# SkyKontrol-slotExpansion.net
KiCad netlist of a schematic drawn in EAGLE
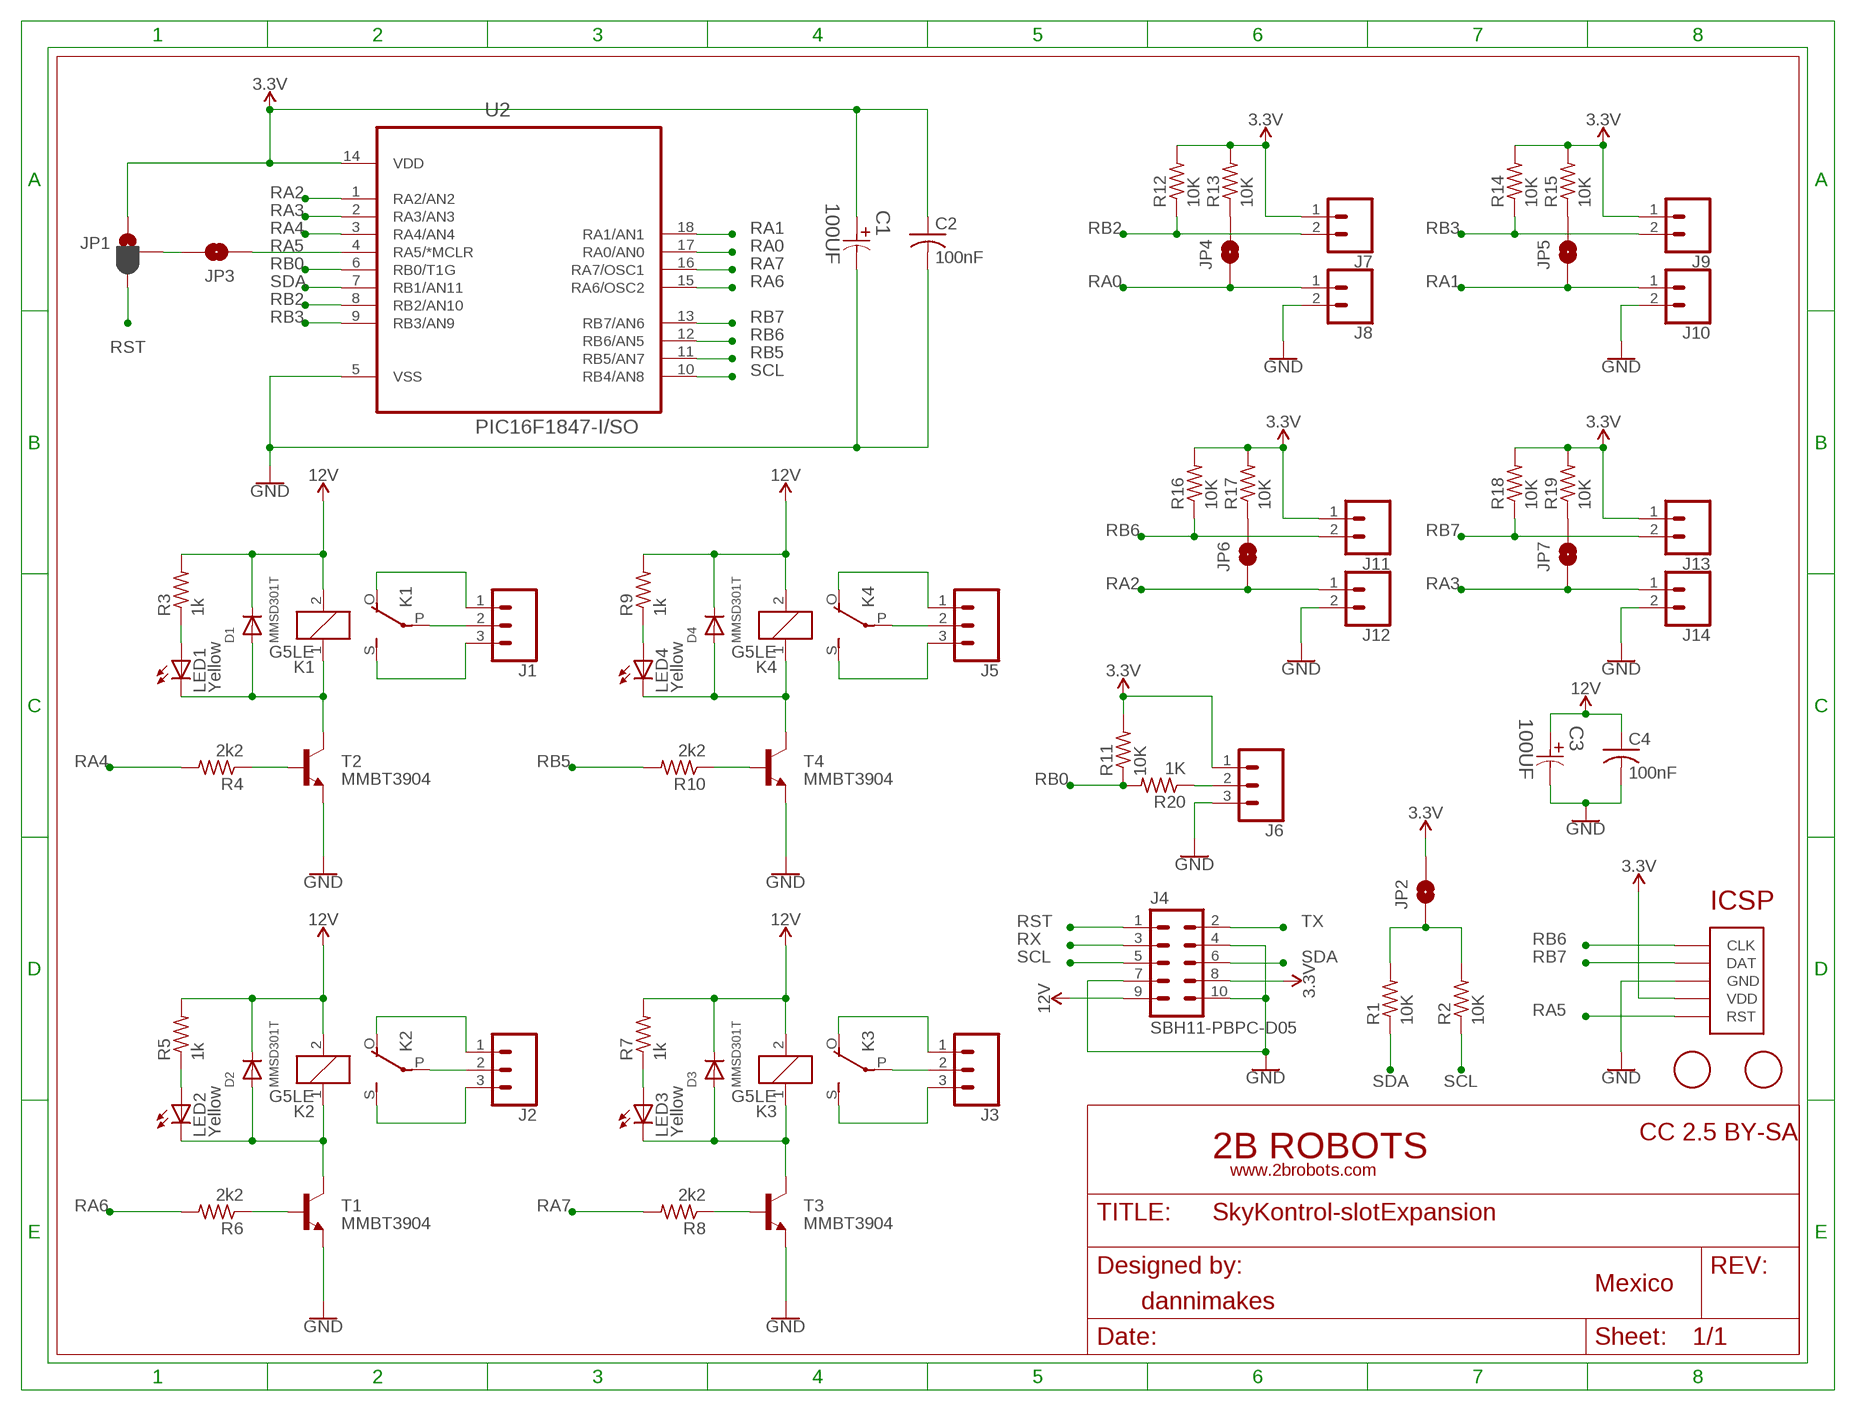
[diagram p0: schematic, sheet 1]

(export (version "E")
  (design (tool "Eeschema 10.0.6"))
  (components
    (comp (ref "C1")
      (value "100UF")
      (footprint "eagle-import:CAPAE660X800N")
      (fields (field (name "MPN") "EEE-HA1E101XP") (field (name "TOLERANCE") "±20 %"))
      (libsource (lib "eagle-import") (part "EEE--CASE-D8HA1E101XP"))
    )
    (comp (ref "C2")
      (value "100nF")
      (footprint "eagle-import:C0603K")
      (libsource (lib "eagle-import") (part "C-USC0603K"))
    )
    (comp (ref "C3")
      (value "100UF")
      (footprint "eagle-import:CAPAE660X800N")
      (fields (field (name "MPN") "EEE-HA1E101XP") (field (name "TOLERANCE") "±20 %"))
      (libsource (lib "eagle-import") (part "EEE--CASE-D8HA1E101XP"))
    )
    (comp (ref "C4")
      (value "100nF")
      (footprint "eagle-import:C0603K")
      (libsource (lib "eagle-import") (part "C-USC0603K"))
    )
    (comp (ref "D1")
      (value "MMSD301T")
      (footprint "eagle-import:SOD-123")
      (libsource (lib "eagle-import") (part "DIODESOD-123"))
    )
    (comp (ref "D2")
      (value "MMSD301T")
      (footprint "eagle-import:SOD-123")
      (libsource (lib "eagle-import") (part "DIODESOD-123"))
    )
    (comp (ref "D3")
      (value "MMSD301T")
      (footprint "eagle-import:SOD-123")
      (libsource (lib "eagle-import") (part "DIODESOD-123"))
    )
    (comp (ref "D4")
      (value "MMSD301T")
      (footprint "eagle-import:SOD-123")
      (libsource (lib "eagle-import") (part "DIODESOD-123"))
    )
    (comp (ref "J1")
      (value "CONN_03-SCREW-5MM")
      (footprint "eagle-import:SCREWTERMINAL-5MM-3")
      (libsource (lib "eagle-import") (part "CONN_03-SCREW-5MM"))
    )
    (comp (ref "J2")
      (value "CONN_03-SCREW-5MM")
      (footprint "eagle-import:SCREWTERMINAL-5MM-3")
      (libsource (lib "eagle-import") (part "CONN_03-SCREW-5MM"))
    )
    (comp (ref "J3")
      (value "CONN_03-SCREW-5MM")
      (footprint "eagle-import:SCREWTERMINAL-5MM-3")
      (libsource (lib "eagle-import") (part "CONN_03-SCREW-5MM"))
    )
    (comp (ref "J4")
      (value "SBH11-PBPC-D05")
      (footprint "eagle-import:SBH11-PBPC-D05")
      (libsource (lib "eagle-import") (part "SBH11-PBPC-D05"))
    )
    (comp (ref "J5")
      (value "CONN_03-SCREW-5MM")
      (footprint "eagle-import:SCREWTERMINAL-5MM-3")
      (libsource (lib "eagle-import") (part "CONN_03-SCREW-5MM"))
    )
    (comp (ref "J6")
      (value "CONN_03-SCREW-5MM")
      (footprint "eagle-import:SCREWTERMINAL-5MM-3")
      (libsource (lib "eagle-import") (part "CONN_03-SCREW-5MM"))
    )
    (comp (ref "J7")
      (value "CONN_025MM")
      (footprint "eagle-import:SCREWTERMINAL-5MM-2")
      (libsource (lib "eagle-import") (part "CONN_025MM"))
    )
    (comp (ref "J8")
      (value "CONN_025MM")
      (footprint "eagle-import:SCREWTERMINAL-5MM-2")
      (libsource (lib "eagle-import") (part "CONN_025MM"))
    )
    (comp (ref "J9")
      (value "CONN_025MM")
      (footprint "eagle-import:SCREWTERMINAL-5MM-2")
      (libsource (lib "eagle-import") (part "CONN_025MM"))
    )
    (comp (ref "J10")
      (value "CONN_025MM")
      (footprint "eagle-import:SCREWTERMINAL-5MM-2")
      (libsource (lib "eagle-import") (part "CONN_025MM"))
    )
    (comp (ref "J11")
      (value "CONN_025MM")
      (footprint "eagle-import:SCREWTERMINAL-5MM-2")
      (libsource (lib "eagle-import") (part "CONN_025MM"))
    )
    (comp (ref "J12")
      (value "CONN_025MM")
      (footprint "eagle-import:SCREWTERMINAL-5MM-2")
      (libsource (lib "eagle-import") (part "CONN_025MM"))
    )
    (comp (ref "J13")
      (value "CONN_025MM")
      (footprint "eagle-import:SCREWTERMINAL-5MM-2")
      (libsource (lib "eagle-import") (part "CONN_025MM"))
    )
    (comp (ref "J14")
      (value "CONN_025MM")
      (footprint "eagle-import:SCREWTERMINAL-5MM-2")
      (libsource (lib "eagle-import") (part "CONN_025MM"))
    )
    (comp (ref "JP1")
      (value "JUMPER-SMT_3_1-NC_PASTE_SILK")
      (footprint "eagle-import:SMT-JUMPER_3_1-NC_PASTE_SILK")
      (libsource (lib "eagle-import") (part "JUMPER-SMT_3_1-NC_PASTE_SILK"))
    )
    (comp (ref "JP2")
      (value "JUMPER-SMT_2_NO_SILK")
      (footprint "eagle-import:SMT-JUMPER_2_NO_SILK")
      (libsource (lib "eagle-import") (part "JUMPER-SMT_2_NO_SILK"))
    )
    (comp (ref "JP3")
      (value "JUMPER-SMT_2_NO_SILK")
      (footprint "eagle-import:SMT-JUMPER_2_NO_SILK")
      (libsource (lib "eagle-import") (part "JUMPER-SMT_2_NO_SILK"))
    )
    (comp (ref "JP4")
      (value "JUMPER-SMT_2_NO_SILK")
      (footprint "eagle-import:SMT-JUMPER_2_NO_SILK")
      (libsource (lib "eagle-import") (part "JUMPER-SMT_2_NO_SILK"))
    )
    (comp (ref "JP5")
      (value "JUMPER-SMT_2_NO_SILK")
      (footprint "eagle-import:SMT-JUMPER_2_NO_SILK")
      (libsource (lib "eagle-import") (part "JUMPER-SMT_2_NO_SILK"))
    )
    (comp (ref "JP6")
      (value "JUMPER-SMT_2_NO_SILK")
      (footprint "eagle-import:SMT-JUMPER_2_NO_SILK")
      (libsource (lib "eagle-import") (part "JUMPER-SMT_2_NO_SILK"))
    )
    (comp (ref "JP7")
      (value "JUMPER-SMT_2_NO_SILK")
      (footprint "eagle-import:SMT-JUMPER_2_NO_SILK")
      (libsource (lib "eagle-import") (part "JUMPER-SMT_2_NO_SILK"))
    )
    (comp (ref "K1")
      (value "G5LE")
      (footprint "eagle-import:G5LE")
      (libsource (lib "eagle-import") (part "G5LE"))
    )
    (comp (ref "K2")
      (value "G5LE")
      (footprint "eagle-import:G5LE")
      (libsource (lib "eagle-import") (part "G5LE"))
    )
    (comp (ref "K3")
      (value "G5LE")
      (footprint "eagle-import:G5LE")
      (libsource (lib "eagle-import") (part "G5LE"))
    )
    (comp (ref "K4")
      (value "G5LE")
      (footprint "eagle-import:G5LE")
      (libsource (lib "eagle-import") (part "G5LE"))
    )
    (comp (ref "LED1")
      (value "Yellow")
      (footprint "eagle-import:CHIPLED_1206")
      (libsource (lib "eagle-import") (part "LEDCHIPLED_1206"))
    )
    (comp (ref "LED2")
      (value "Yellow")
      (footprint "eagle-import:CHIPLED_1206")
      (libsource (lib "eagle-import") (part "LEDCHIPLED_1206"))
    )
    (comp (ref "LED3")
      (value "Yellow")
      (footprint "eagle-import:CHIPLED_1206")
      (libsource (lib "eagle-import") (part "LEDCHIPLED_1206"))
    )
    (comp (ref "LED4")
      (value "Yellow")
      (footprint "eagle-import:CHIPLED_1206")
      (libsource (lib "eagle-import") (part "LEDCHIPLED_1206"))
    )
    (comp (ref "R1")
      (value "10K")
      (footprint "eagle-import:R0805")
      (libsource (lib "eagle-import") (part "R-US_R0805"))
    )
    (comp (ref "R2")
      (value "10K")
      (footprint "eagle-import:R0805")
      (libsource (lib "eagle-import") (part "R-US_R0805"))
    )
    (comp (ref "R3")
      (value "1k")
      (footprint "eagle-import:R0805")
      (libsource (lib "eagle-import") (part "R-US_R0805"))
    )
    (comp (ref "R4")
      (value "2k2")
      (footprint "eagle-import:R0805")
      (libsource (lib "eagle-import") (part "R-US_R0805"))
    )
    (comp (ref "R5")
      (value "1k")
      (footprint "eagle-import:R0805")
      (libsource (lib "eagle-import") (part "R-US_R0805"))
    )
    (comp (ref "R6")
      (value "2k2")
      (footprint "eagle-import:R0805")
      (libsource (lib "eagle-import") (part "R-US_R0805"))
    )
    (comp (ref "R7")
      (value "1k")
      (footprint "eagle-import:R0805")
      (libsource (lib "eagle-import") (part "R-US_R0805"))
    )
    (comp (ref "R8")
      (value "2k2")
      (footprint "eagle-import:R0805")
      (libsource (lib "eagle-import") (part "R-US_R0805"))
    )
    (comp (ref "R9")
      (value "1k")
      (footprint "eagle-import:R0805")
      (libsource (lib "eagle-import") (part "R-US_R0805"))
    )
    (comp (ref "R10")
      (value "2k2")
      (footprint "eagle-import:R0805")
      (libsource (lib "eagle-import") (part "R-US_R0805"))
    )
    (comp (ref "R11")
      (value "10K")
      (footprint "eagle-import:R0805")
      (libsource (lib "eagle-import") (part "R-US_R0805"))
    )
    (comp (ref "R12")
      (value "10K")
      (footprint "eagle-import:R0805")
      (libsource (lib "eagle-import") (part "R-US_R0805"))
    )
    (comp (ref "R13")
      (value "10K")
      (footprint "eagle-import:R0805")
      (libsource (lib "eagle-import") (part "R-US_R0805"))
    )
    (comp (ref "R14")
      (value "10K")
      (footprint "eagle-import:R0805")
      (libsource (lib "eagle-import") (part "R-US_R0805"))
    )
    (comp (ref "R15")
      (value "10K")
      (footprint "eagle-import:R0805")
      (libsource (lib "eagle-import") (part "R-US_R0805"))
    )
    (comp (ref "R16")
      (value "10K")
      (footprint "eagle-import:R0805")
      (libsource (lib "eagle-import") (part "R-US_R0805"))
    )
    (comp (ref "R17")
      (value "10K")
      (footprint "eagle-import:R0805")
      (libsource (lib "eagle-import") (part "R-US_R0805"))
    )
    (comp (ref "R18")
      (value "10K")
      (footprint "eagle-import:R0805")
      (libsource (lib "eagle-import") (part "R-US_R0805"))
    )
    (comp (ref "R19")
      (value "10K")
      (footprint "eagle-import:R0805")
      (libsource (lib "eagle-import") (part "R-US_R0805"))
    )
    (comp (ref "R20")
      (value "1K")
      (footprint "eagle-import:R0805")
      (libsource (lib "eagle-import") (part "R-US_R0805"))
    )
    (comp (ref "T1")
      (value "MMBT3904")
      (footprint "eagle-import:SOT23-BEC")
      (libsource (lib "eagle-import") (part "-NPN-SOT23-BECMMBT3904LT1"))
    )
    (comp (ref "T2")
      (value "MMBT3904")
      (footprint "eagle-import:SOT23-BEC")
      (libsource (lib "eagle-import") (part "-NPN-SOT23-BECMMBT3904LT1"))
    )
    (comp (ref "T3")
      (value "MMBT3904")
      (footprint "eagle-import:SOT23-BEC")
      (libsource (lib "eagle-import") (part "-NPN-SOT23-BECMMBT3904LT1"))
    )
    (comp (ref "T4")
      (value "MMBT3904")
      (footprint "eagle-import:SOT23-BEC")
      (libsource (lib "eagle-import") (part "-NPN-SOT23-BECMMBT3904LT1"))
    )
    (comp (ref "U$1")
      (value "FIDUCIAL")
      (footprint "eagle-import:FIDUCIAL_1MM")
      (libsource (lib "eagle-import") (part "FIDUCIAL"))
    )
    (comp (ref "U$2")
      (value "ICSP_POGO")
      (footprint "eagle-import:ICSP_POGO")
      (libsource (lib "eagle-import") (part "ICSP_POGO"))
    )
    (comp (ref "U$3")
      (value "FIDUCIAL")
      (footprint "eagle-import:FIDUCIAL_1MM")
      (libsource (lib "eagle-import") (part "FIDUCIAL"))
    )
    (comp (ref "U2")
      (value "PIC16F1847-I/SO")
      (footprint "eagle-import:SOIC127P1030X265-18N")
      (libsource (lib "eagle-import") (part "PIC16F1847-I/SO"))
    )
  )
  (nets
    (net (code "1") (name "/RA0") (class "Default")
      (node (ref "J8") (pin "1") (pinfunction "1_1") (pintype "passive"))
      (node (ref "JP4") (pin "1") (pinfunction "1_1") (pintype "passive"))
      (node (ref "U2") (pin "17") (pinfunction "RA0/AN0_17") (pintype "bidirectional"))
    )
    (net (code "2") (name "/RA1") (class "Default")
      (node (ref "J10") (pin "1") (pinfunction "1_1") (pintype "passive"))
      (node (ref "JP5") (pin "1") (pinfunction "1_1") (pintype "passive"))
      (node (ref "U2") (pin "18") (pinfunction "RA1/AN1_18") (pintype "bidirectional"))
    )
    (net (code "3") (name "/RA2") (class "Default")
      (node (ref "J12") (pin "1") (pinfunction "1_1") (pintype "passive"))
      (node (ref "JP6") (pin "1") (pinfunction "1_1") (pintype "passive"))
      (node (ref "U2") (pin "1") (pinfunction "RA2/AN2_1") (pintype "bidirectional"))
    )
    (net (code "4") (name "/RA3") (class "Default")
      (node (ref "J14") (pin "1") (pinfunction "1_1") (pintype "passive"))
      (node (ref "JP7") (pin "1") (pinfunction "1_1") (pintype "passive"))
      (node (ref "U2") (pin "2") (pinfunction "RA3/AN3_2") (pintype "bidirectional"))
    )
    (net (code "5") (name "/RA4") (class "Default")
      (node (ref "R4") (pin "2") (pinfunction "2_2") (pintype "passive"))
      (node (ref "U2") (pin "3") (pinfunction "RA4/AN4_3") (pintype "bidirectional"))
    )
    (net (code "6") (name "/RA5") (class "Default")
      (node (ref "JP3") (pin "1") (pinfunction "1_1") (pintype "passive"))
      (node (ref "U$2") (pin "P$1") (pinfunction "RST_P$1") (pintype "bidirectional"))
      (node (ref "U2") (pin "4") (pinfunction "RA5/*MCLR_4") (pintype "bidirectional"))
    )
    (net (code "7") (name "/RA6") (class "Default")
      (node (ref "R6") (pin "2") (pinfunction "2_2") (pintype "passive"))
      (node (ref "U2") (pin "15") (pinfunction "RA6/OSC2_15") (pintype "bidirectional"))
    )
    (net (code "8") (name "/RA7") (class "Default")
      (node (ref "R8") (pin "2") (pinfunction "2_2") (pintype "passive"))
      (node (ref "U2") (pin "16") (pinfunction "RA7/OSC1_16") (pintype "bidirectional"))
    )
    (net (code "9") (name "/RB0") (class "Default")
      (node (ref "R11") (pin "1") (pinfunction "1_1") (pintype "passive"))
      (node (ref "R20") (pin "2") (pinfunction "2_2") (pintype "passive"))
      (node (ref "U2") (pin "6") (pinfunction "RB0/T1G_6") (pintype "bidirectional"))
    )
    (net (code "10") (name "/RB2") (class "Default")
      (node (ref "J7") (pin "2") (pinfunction "2_2") (pintype "passive"))
      (node (ref "R12") (pin "1") (pinfunction "1_1") (pintype "passive"))
      (node (ref "U2") (pin "8") (pinfunction "RB2/AN10_8") (pintype "bidirectional"))
    )
    (net (code "11") (name "/RB3") (class "Default")
      (node (ref "J9") (pin "2") (pinfunction "2_2") (pintype "passive"))
      (node (ref "R14") (pin "1") (pinfunction "1_1") (pintype "passive"))
      (node (ref "U2") (pin "9") (pinfunction "RB3/AN9_9") (pintype "bidirectional"))
    )
    (net (code "12") (name "/RB5") (class "Default")
      (node (ref "R10") (pin "2") (pinfunction "2_2") (pintype "passive"))
      (node (ref "U2") (pin "11") (pinfunction "RB5/AN7_11") (pintype "bidirectional"))
    )
    (net (code "13") (name "/RB6") (class "Default")
      (node (ref "J11") (pin "2") (pinfunction "2_2") (pintype "passive"))
      (node (ref "R16") (pin "1") (pinfunction "1_1") (pintype "passive"))
      (node (ref "U$2") (pin "P$5") (pinfunction "CLK_P$5") (pintype "bidirectional"))
      (node (ref "U2") (pin "12") (pinfunction "RB6/AN5_12") (pintype "bidirectional"))
    )
    (net (code "14") (name "/RB7") (class "Default")
      (node (ref "J13") (pin "2") (pinfunction "2_2") (pintype "passive"))
      (node (ref "R18") (pin "1") (pinfunction "1_1") (pintype "passive"))
      (node (ref "U$2") (pin "P$4") (pinfunction "DAT_P$4") (pintype "bidirectional"))
      (node (ref "U2") (pin "13") (pinfunction "RB7/AN6_13") (pintype "bidirectional"))
    )
    (net (code "15") (name "/RST") (class "Default")
      (node (ref "J4") (pin "1") (pinfunction "1_1") (pintype "passive"))
      (node (ref "JP1") (pin "3") (pinfunction "3_3") (pintype "passive"))
    )
    (net (code "16") (name "/RX") (class "Default")
      (node (ref "J4") (pin "3") (pinfunction "3_3") (pintype "passive"))
    )
    (net (code "17") (name "/SCL") (class "Default")
      (node (ref "J4") (pin "5") (pinfunction "5_5") (pintype "passive"))
      (node (ref "R2") (pin "1") (pinfunction "1_1") (pintype "passive"))
      (node (ref "U2") (pin "10") (pinfunction "RB4/AN8_10") (pintype "bidirectional"))
    )
    (net (code "18") (name "/SDA") (class "Default")
      (node (ref "J4") (pin "6") (pinfunction "6_6") (pintype "passive"))
      (node (ref "R1") (pin "1") (pinfunction "1_1") (pintype "passive"))
      (node (ref "U2") (pin "7") (pinfunction "RB1/AN11_7") (pintype "bidirectional"))
    )
    (net (code "19") (name "/TX") (class "Default")
      (node (ref "J4") (pin "2") (pinfunction "2_2") (pintype "passive"))
    )
    (net (code "20") (name "3.3V") (class "Default")
      (node (ref "C1") (pin "1") (pinfunction "1_1") (pintype "passive"))
      (node (ref "C2") (pin "1") (pinfunction "1_1") (pintype "passive"))
      (node (ref "J11") (pin "1") (pinfunction "1_1") (pintype "passive"))
      (node (ref "J13") (pin "1") (pinfunction "1_1") (pintype "passive"))
      (node (ref "J4") (pin "8") (pinfunction "8_8") (pintype "passive"))
      (node (ref "J6") (pin "1") (pinfunction "1_1") (pintype "passive"))
      (node (ref "J7") (pin "1") (pinfunction "1_1") (pintype "passive"))
      (node (ref "J9") (pin "1") (pinfunction "1_1") (pintype "passive"))
      (node (ref "JP1") (pin "1") (pinfunction "1_1") (pintype "passive"))
      (node (ref "JP2") (pin "2") (pinfunction "2_2") (pintype "passive"))
      (node (ref "R11") (pin "2") (pinfunction "2_2") (pintype "passive"))
      (node (ref "R12") (pin "2") (pinfunction "2_2") (pintype "passive"))
      (node (ref "R13") (pin "2") (pinfunction "2_2") (pintype "passive"))
      (node (ref "R14") (pin "2") (pinfunction "2_2") (pintype "passive"))
      (node (ref "R15") (pin "2") (pinfunction "2_2") (pintype "passive"))
      (node (ref "R16") (pin "2") (pinfunction "2_2") (pintype "passive"))
      (node (ref "R17") (pin "2") (pinfunction "2_2") (pintype "passive"))
      (node (ref "R18") (pin "2") (pinfunction "2_2") (pintype "passive"))
      (node (ref "R19") (pin "2") (pinfunction "2_2") (pintype "passive"))
      (node (ref "U$2") (pin "P$2") (pinfunction "VDD_P$2") (pintype "bidirectional"))
      (node (ref "U2") (pin "14") (pinfunction "VDD_14") (pintype "power_in"))
    )
    (net (code "21") (name "12V") (class "Default")
      (node (ref "C3") (pin "1") (pinfunction "1_1") (pintype "passive"))
      (node (ref "C4") (pin "1") (pinfunction "1_1") (pintype "passive"))
      (node (ref "D1") (pin "C") (pinfunction "C_C") (pintype "passive"))
      (node (ref "D2") (pin "C") (pinfunction "C_C") (pintype "passive"))
      (node (ref "D3") (pin "C") (pinfunction "C_C") (pintype "passive"))
      (node (ref "D4") (pin "C") (pinfunction "C_C") (pintype "passive"))
      (node (ref "J4") (pin "9") (pinfunction "9_9") (pintype "passive"))
      (node (ref "K1") (pin "2") (pinfunction "2_2") (pintype "passive"))
      (node (ref "K2") (pin "2") (pinfunction "2_2") (pintype "passive"))
      (node (ref "K3") (pin "2") (pinfunction "2_2") (pintype "passive"))
      (node (ref "K4") (pin "2") (pinfunction "2_2") (pintype "passive"))
      (node (ref "R3") (pin "2") (pinfunction "2_2") (pintype "passive"))
      (node (ref "R5") (pin "2") (pinfunction "2_2") (pintype "passive"))
      (node (ref "R7") (pin "2") (pinfunction "2_2") (pintype "passive"))
      (node (ref "R9") (pin "2") (pinfunction "2_2") (pintype "passive"))
    )
    (net (code "22") (name "GND") (class "Default")
      (node (ref "C1") (pin "2") (pinfunction "2_2") (pintype "passive"))
      (node (ref "C2") (pin "2") (pinfunction "2_2") (pintype "passive"))
      (node (ref "C3") (pin "2") (pinfunction "2_2") (pintype "passive"))
      (node (ref "C4") (pin "2") (pinfunction "2_2") (pintype "passive"))
      (node (ref "J10") (pin "2") (pinfunction "2_2") (pintype "passive"))
      (node (ref "J12") (pin "2") (pinfunction "2_2") (pintype "passive"))
      (node (ref "J14") (pin "2") (pinfunction "2_2") (pintype "passive"))
      (node (ref "J4") (pin "10") (pinfunction "10_10") (pintype "passive"))
      (node (ref "J4") (pin "4") (pinfunction "4_4") (pintype "passive"))
      (node (ref "J4") (pin "7") (pinfunction "7_7") (pintype "passive"))
      (node (ref "J6") (pin "3") (pinfunction "3_3") (pintype "passive"))
      (node (ref "J8") (pin "2") (pinfunction "2_2") (pintype "passive"))
      (node (ref "T1") (pin "E") (pinfunction "E_E") (pintype "passive"))
      (node (ref "T2") (pin "E") (pinfunction "E_E") (pintype "passive"))
      (node (ref "T3") (pin "E") (pinfunction "E_E") (pintype "passive"))
      (node (ref "T4") (pin "E") (pinfunction "E_E") (pintype "passive"))
      (node (ref "U$2") (pin "P$3") (pinfunction "GND_P$3") (pintype "bidirectional"))
      (node (ref "U2") (pin "5") (pinfunction "VSS_5") (pintype "power_in"))
    )
    (net (code "23") (name "Net-(D1-PadA)") (class "Default")
      (node (ref "D1") (pin "A") (pinfunction "A_A") (pintype "passive"))
      (node (ref "K1") (pin "1") (pinfunction "1_1") (pintype "passive"))
      (node (ref "LED1") (pin "C") (pinfunction "C_C") (pintype "passive"))
      (node (ref "T2") (pin "C") (pinfunction "C_C") (pintype "passive"))
    )
    (net (code "24") (name "Net-(D2-PadA)") (class "Default")
      (node (ref "D2") (pin "A") (pinfunction "A_A") (pintype "passive"))
      (node (ref "K2") (pin "1") (pinfunction "1_1") (pintype "passive"))
      (node (ref "LED2") (pin "C") (pinfunction "C_C") (pintype "passive"))
      (node (ref "T1") (pin "C") (pinfunction "C_C") (pintype "passive"))
    )
    (net (code "25") (name "Net-(D3-PadA)") (class "Default")
      (node (ref "D3") (pin "A") (pinfunction "A_A") (pintype "passive"))
      (node (ref "K3") (pin "1") (pinfunction "1_1") (pintype "passive"))
      (node (ref "LED3") (pin "C") (pinfunction "C_C") (pintype "passive"))
      (node (ref "T3") (pin "C") (pinfunction "C_C") (pintype "passive"))
    )
    (net (code "26") (name "Net-(D4-PadA)") (class "Default")
      (node (ref "D4") (pin "A") (pinfunction "A_A") (pintype "passive"))
      (node (ref "K4") (pin "1") (pinfunction "1_1") (pintype "passive"))
      (node (ref "LED4") (pin "C") (pinfunction "C_C") (pintype "passive"))
      (node (ref "T4") (pin "C") (pinfunction "C_C") (pintype "passive"))
    )
    (net (code "27") (name "Net-(J1-Pad1)") (class "Default")
      (node (ref "J1") (pin "1") (pinfunction "1_1") (pintype "passive"))
      (node (ref "K1") (pin "O") (pinfunction "O_O") (pintype "passive"))
    )
    (net (code "28") (name "Net-(J1-Pad2)") (class "Default")
      (node (ref "J1") (pin "2") (pinfunction "2_2") (pintype "passive"))
      (node (ref "K1") (pin "P") (pinfunction "P_P") (pintype "passive"))
    )
    (net (code "29") (name "Net-(J1-Pad3)") (class "Default")
      (node (ref "J1") (pin "3") (pinfunction "3_3") (pintype "passive"))
      (node (ref "K1") (pin "S") (pinfunction "S_S") (pintype "passive"))
    )
    (net (code "30") (name "Net-(J2-Pad1)") (class "Default")
      (node (ref "J2") (pin "1") (pinfunction "1_1") (pintype "passive"))
      (node (ref "K2") (pin "O") (pinfunction "O_O") (pintype "passive"))
    )
    (net (code "31") (name "Net-(J2-Pad2)") (class "Default")
      (node (ref "J2") (pin "2") (pinfunction "2_2") (pintype "passive"))
      (node (ref "K2") (pin "P") (pinfunction "P_P") (pintype "passive"))
    )
    (net (code "32") (name "Net-(J2-Pad3)") (class "Default")
      (node (ref "J2") (pin "3") (pinfunction "3_3") (pintype "passive"))
      (node (ref "K2") (pin "S") (pinfunction "S_S") (pintype "passive"))
    )
    (net (code "33") (name "Net-(J3-Pad1)") (class "Default")
      (node (ref "J3") (pin "1") (pinfunction "1_1") (pintype "passive"))
      (node (ref "K3") (pin "O") (pinfunction "O_O") (pintype "passive"))
    )
    (net (code "34") (name "Net-(J3-Pad2)") (class "Default")
      (node (ref "J3") (pin "2") (pinfunction "2_2") (pintype "passive"))
      (node (ref "K3") (pin "P") (pinfunction "P_P") (pintype "passive"))
    )
    (net (code "35") (name "Net-(J3-Pad3)") (class "Default")
      (node (ref "J3") (pin "3") (pinfunction "3_3") (pintype "passive"))
      (node (ref "K3") (pin "S") (pinfunction "S_S") (pintype "passive"))
    )
    (net (code "36") (name "Net-(J5-Pad1)") (class "Default")
      (node (ref "J5") (pin "1") (pinfunction "1_1") (pintype "passive"))
      (node (ref "K4") (pin "O") (pinfunction "O_O") (pintype "passive"))
    )
    (net (code "37") (name "Net-(J5-Pad2)") (class "Default")
      (node (ref "J5") (pin "2") (pinfunction "2_2") (pintype "passive"))
      (node (ref "K4") (pin "P") (pinfunction "P_P") (pintype "passive"))
    )
    (net (code "38") (name "Net-(J5-Pad3)") (class "Default")
      (node (ref "J5") (pin "3") (pinfunction "3_3") (pintype "passive"))
      (node (ref "K4") (pin "S") (pinfunction "S_S") (pintype "passive"))
    )
    (net (code "39") (name "Net-(J6-Pad2)") (class "Default")
      (node (ref "J6") (pin "2") (pinfunction "2_2") (pintype "passive"))
      (node (ref "R20") (pin "1") (pinfunction "1_1") (pintype "passive"))
    )
    (net (code "40") (name "Net-(JP1-Pad2)") (class "Default")
      (node (ref "JP1") (pin "2") (pinfunction "2_2") (pintype "passive"))
      (node (ref "JP3") (pin "2") (pinfunction "2_2") (pintype "passive"))
    )
    (net (code "41") (name "Net-(JP2-Pad1)") (class "Default")
      (node (ref "JP2") (pin "1") (pinfunction "1_1") (pintype "passive"))
      (node (ref "R1") (pin "2") (pinfunction "2_2") (pintype "passive"))
      (node (ref "R2") (pin "2") (pinfunction "2_2") (pintype "passive"))
    )
    (net (code "42") (name "Net-(JP4-Pad2)") (class "Default")
      (node (ref "JP4") (pin "2") (pinfunction "2_2") (pintype "passive"))
      (node (ref "R13") (pin "1") (pinfunction "1_1") (pintype "passive"))
    )
    (net (code "43") (name "Net-(JP5-Pad2)") (class "Default")
      (node (ref "JP5") (pin "2") (pinfunction "2_2") (pintype "passive"))
      (node (ref "R15") (pin "1") (pinfunction "1_1") (pintype "passive"))
    )
    (net (code "44") (name "Net-(JP6-Pad2)") (class "Default")
      (node (ref "JP6") (pin "2") (pinfunction "2_2") (pintype "passive"))
      (node (ref "R17") (pin "1") (pinfunction "1_1") (pintype "passive"))
    )
    (net (code "45") (name "Net-(JP7-Pad2)") (class "Default")
      (node (ref "JP7") (pin "2") (pinfunction "2_2") (pintype "passive"))
      (node (ref "R19") (pin "1") (pinfunction "1_1") (pintype "passive"))
    )
    (net (code "46") (name "Net-(LED1-PadA)") (class "Default")
      (node (ref "LED1") (pin "A") (pinfunction "A_A") (pintype "passive"))
      (node (ref "R3") (pin "1") (pinfunction "1_1") (pintype "passive"))
    )
    (net (code "47") (name "Net-(LED2-PadA)") (class "Default")
      (node (ref "LED2") (pin "A") (pinfunction "A_A") (pintype "passive"))
      (node (ref "R5") (pin "1") (pinfunction "1_1") (pintype "passive"))
    )
    (net (code "48") (name "Net-(LED3-PadA)") (class "Default")
      (node (ref "LED3") (pin "A") (pinfunction "A_A") (pintype "passive"))
      (node (ref "R7") (pin "1") (pinfunction "1_1") (pintype "passive"))
    )
    (net (code "49") (name "Net-(LED4-PadA)") (class "Default")
      (node (ref "LED4") (pin "A") (pinfunction "A_A") (pintype "passive"))
      (node (ref "R9") (pin "1") (pinfunction "1_1") (pintype "passive"))
    )
    (net (code "50") (name "Net-(R4-Pad1)") (class "Default")
      (node (ref "R4") (pin "1") (pinfunction "1_1") (pintype "passive"))
      (node (ref "T2") (pin "B") (pinfunction "B_B") (pintype "passive"))
    )
    (net (code "51") (name "Net-(R6-Pad1)") (class "Default")
      (node (ref "R6") (pin "1") (pinfunction "1_1") (pintype "passive"))
      (node (ref "T1") (pin "B") (pinfunction "B_B") (pintype "passive"))
    )
    (net (code "52") (name "Net-(R8-Pad1)") (class "Default")
      (node (ref "R8") (pin "1") (pinfunction "1_1") (pintype "passive"))
      (node (ref "T3") (pin "B") (pinfunction "B_B") (pintype "passive"))
    )
    (net (code "53") (name "Net-(R10-Pad1)") (class "Default")
      (node (ref "R10") (pin "1") (pinfunction "1_1") (pintype "passive"))
      (node (ref "T4") (pin "B") (pinfunction "B_B") (pintype "passive"))
    )
  )
)
